# RFID_reader_circuit.net
KiCad netlist of a schematic drawn in Altium Designer
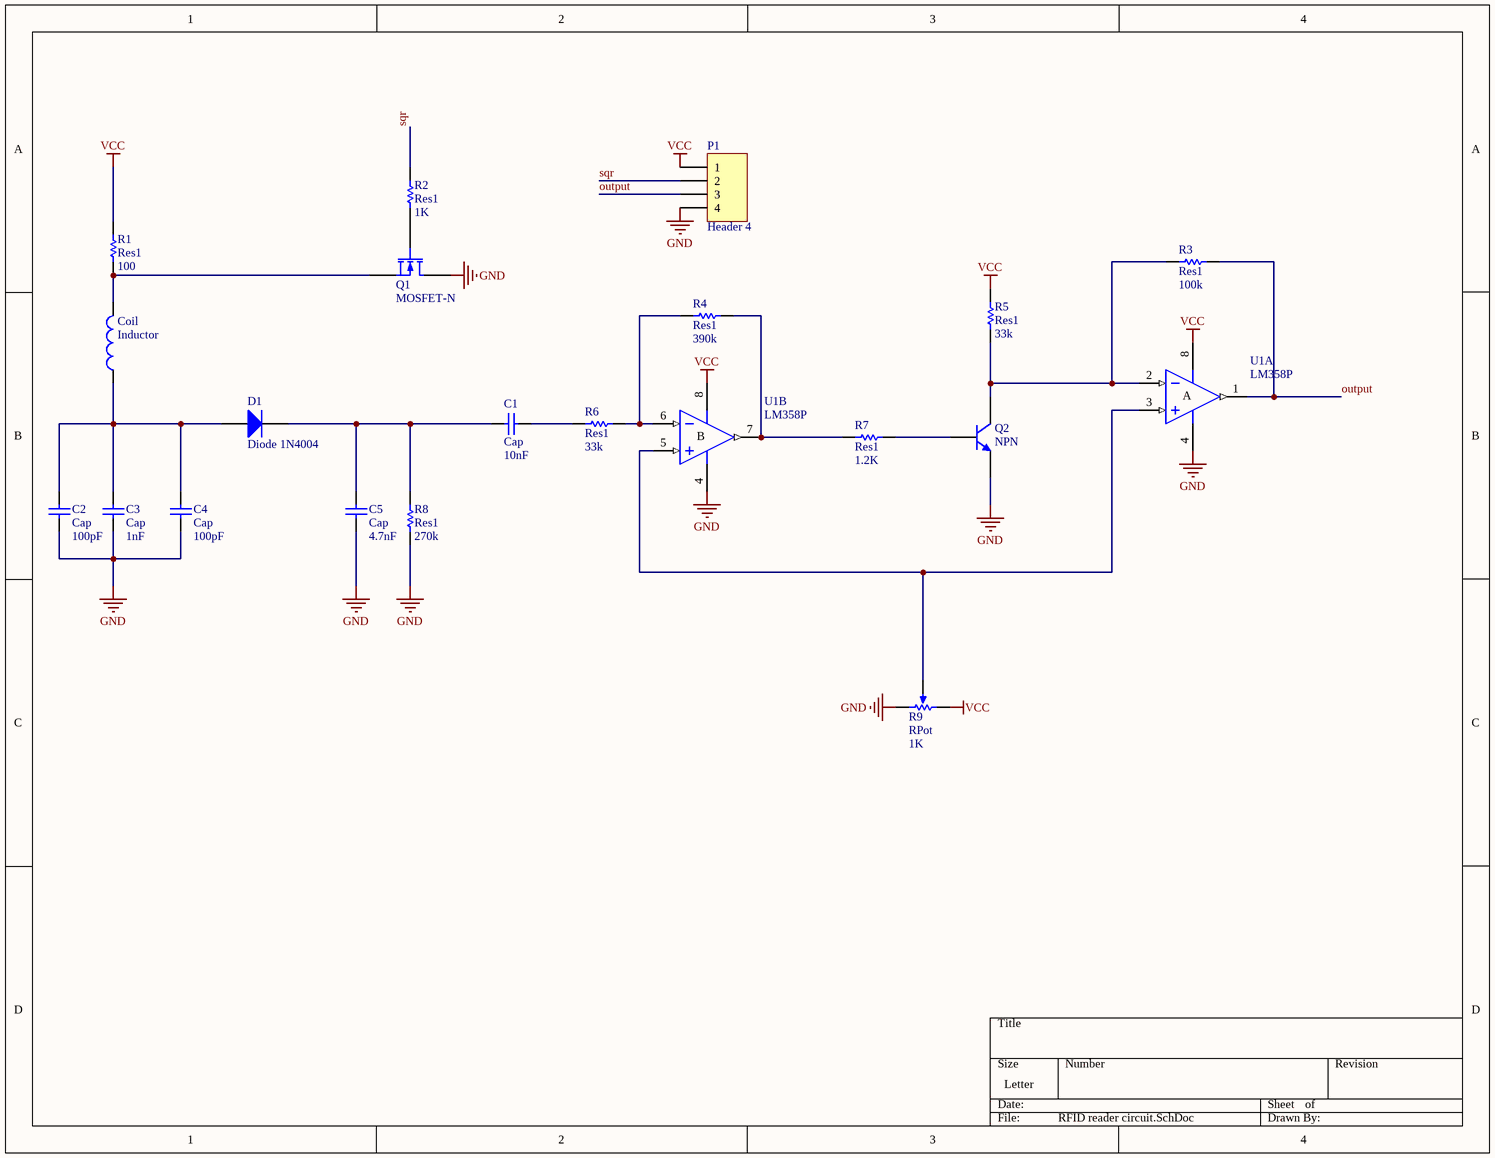
[diagram p0: RFID reader circuit.SchDoc]

(export (version "E")
  (design (tool "Eeschema 10.0.6"))
  (components
    (comp (ref "C1")
      (value "Cap")
      (footprint "RAD-0.3")
      (description "Capacitor")
      (fields (field (name "ALTIUM_VALUE") "10nF") (field (name "PUBLISHER") "Altium Limited"))
      (libsource (lib "Miscellaneous Devices") (part "Cap"))
    )
    (comp (ref "C2")
      (value "Cap")
      (footprint "RAD-0.3")
      (description "Capacitor")
      (fields (field (name "ALTIUM_VALUE") "100pF") (field (name "PUBLISHER") "Altium Limited"))
      (libsource (lib "Miscellaneous Devices") (part "Cap"))
    )
    (comp (ref "C3")
      (value "Cap")
      (footprint "RAD-0.3")
      (description "Capacitor")
      (fields (field (name "ALTIUM_VALUE") "1nF") (field (name "PUBLISHER") "Altium Limited"))
      (libsource (lib "Miscellaneous Devices") (part "Cap"))
    )
    (comp (ref "C4")
      (value "Cap")
      (footprint "RAD-0.3")
      (description "Capacitor")
      (fields (field (name "ALTIUM_VALUE") "100pF") (field (name "PUBLISHER") "Altium Limited"))
      (libsource (lib "Miscellaneous Devices") (part "Cap"))
    )
    (comp (ref "C5")
      (value "Cap")
      (footprint "RAD-0.3")
      (description "Capacitor")
      (fields (field (name "ALTIUM_VALUE") "4.7nF") (field (name "PUBLISHER") "Altium Limited"))
      (libsource (lib "Miscellaneous Devices") (part "Cap"))
    )
    (comp (ref "Coil")
      (value "Inductor")
      (footprint "XTAL-2")
      (fields (field (name "PUBLISHER") "Altium Limited"))
      (libsource (lib "Miscellaneous Devices") (part "Inductor"))
    )
    (comp (ref "D1")
      (value "Diode 1N4004")
      (footprint "DO-41")
      (description "1 Amp General Purpose Rectifier")
      (fields (field (name "PUBLISHER") "Altium Limited"))
      (libsource (lib "Miscellaneous Devices") (part "Diode 1N4004"))
    )
    (comp (ref "P1")
      (value "Header 4")
      (footprint "HDR1X4")
      (description "Header, 4-Pin")
      (fields (field (name "PUBLISHER") "Altium Limited"))
      (libsource (lib "Miscellaneous Connectors") (part "Header 4"))
    )
    (comp (ref "Q1")
      (value "MOSFET-N")
      (footprint "E3")
      (description "N-Channel MOSFET")
      (fields (field (name "PUBLISHER") "Altium Limited"))
      (libsource (lib "Miscellaneous Devices") (part "MOSFET-N"))
    )
    (comp (ref "Q2")
      (value "NPN")
      (footprint "TO-226-AA")
      (description "NPN Bipolar Transistor")
      (fields (field (name "PUBLISHER") "Altium Limited"))
      (libsource (lib "Miscellaneous Devices") (part "NPN"))
    )
    (comp (ref "R1")
      (value "Res1")
      (footprint "AXIAL-0.3")
      (description "Resistor")
      (fields (field (name "ALTIUM_VALUE") "100") (field (name "PUBLISHER") "Altium Limited"))
      (libsource (lib "Miscellaneous Devices") (part "Res1"))
    )
    (comp (ref "R2")
      (value "Res1")
      (footprint "AXIAL-0.3")
      (description "Resistor")
      (fields (field (name "ALTIUM_VALUE") "1K") (field (name "PUBLISHER") "Altium Limited"))
      (libsource (lib "Miscellaneous Devices") (part "Res1"))
    )
    (comp (ref "R3")
      (value "Res1")
      (footprint "AXIAL-0.3")
      (description "Resistor")
      (fields (field (name "ALTIUM_VALUE") "100k") (field (name "PUBLISHER") "Altium Limited"))
      (libsource (lib "Miscellaneous Devices") (part "Res1"))
    )
    (comp (ref "R4")
      (value "Res1")
      (footprint "AXIAL-0.3")
      (description "Resistor")
      (fields (field (name "ALTIUM_VALUE") "390k") (field (name "PUBLISHER") "Altium Limited"))
      (libsource (lib "Miscellaneous Devices") (part "Res1"))
    )
    (comp (ref "R5")
      (value "Res1")
      (footprint "AXIAL-0.3")
      (description "Resistor")
      (fields (field (name "ALTIUM_VALUE") "33k") (field (name "PUBLISHER") "Altium Limited"))
      (libsource (lib "Miscellaneous Devices") (part "Res1"))
    )
    (comp (ref "R6")
      (value "Res1")
      (footprint "AXIAL-0.3")
      (description "Resistor")
      (fields (field (name "ALTIUM_VALUE") "33k") (field (name "PUBLISHER") "Altium Limited"))
      (libsource (lib "Miscellaneous Devices") (part "Res1"))
    )
    (comp (ref "R7")
      (value "Res1")
      (footprint "AXIAL-0.3")
      (description "Resistor")
      (fields (field (name "ALTIUM_VALUE") "1.2K") (field (name "PUBLISHER") "Altium Limited"))
      (libsource (lib "Miscellaneous Devices") (part "Res1"))
    )
    (comp (ref "R8")
      (value "Res1")
      (footprint "AXIAL-0.3")
      (description "Resistor")
      (fields (field (name "ALTIUM_VALUE") "270k") (field (name "PUBLISHER") "Altium Limited"))
      (libsource (lib "Miscellaneous Devices") (part "Res1"))
    )
    (comp (ref "R9")
      (value "RPot")
      (footprint "VR5")
      (description "Potentiometer")
      (fields (field (name "ALTIUM_VALUE") "1K") (field (name "PUBLISHER") "Altium Limited"))
      (libsource (lib "Miscellaneous Devices") (part "RPot"))
    )
    (comp (ref "U1")
      (value "LM358P")
      (footprint "P008")
      (description "Dual Operational Amplifier")
      (fields (field (name "PUBLISHER") "Altium Limited"))
      (libsource (lib "TI Operational Amplifier") (part "LM358P"))
    )
  )
  (nets
    (net (code "1") (name "/output") (class "Default")
      (node (ref "P1") (pin "3") (pinfunction "3_3") (pintype "passive"))
      (node (ref "R3") (pin "1") (pinfunction "1_1") (pintype "passive"))
      (node (ref "U1") (pin "1") (pinfunction "OUT_1") (pintype "output"))
    )
    (net (code "2") (name "/sqr") (class "Default")
      (node (ref "P1") (pin "2") (pinfunction "2_2") (pintype "passive"))
      (node (ref "R2") (pin "2") (pinfunction "2_2") (pintype "passive"))
    )
    (net (code "3") (name "GND") (class "Default")
      (node (ref "C2") (pin "1") (pinfunction "1_1") (pintype "passive"))
      (node (ref "C3") (pin "1") (pinfunction "1_1") (pintype "passive"))
      (node (ref "C4") (pin "1") (pinfunction "1_1") (pintype "passive"))
      (node (ref "C5") (pin "1") (pinfunction "1_1") (pintype "passive"))
      (node (ref "P1") (pin "4") (pinfunction "4_4") (pintype "passive"))
      (node (ref "Q1") (pin "1") (pinfunction "D_1") (pintype "passive"))
      (node (ref "Q2") (pin "3") (pinfunction "E_3") (pintype "passive"))
      (node (ref "R8") (pin "2") (pinfunction "2_2") (pintype "passive"))
      (node (ref "R9") (pin "2") (pinfunction "BOT_2") (pintype "passive"))
      (node (ref "U1") (pin "4") (pinfunction "V-_4") (pintype "power_in"))
    )
    (net (code "4") (name "Net-(C1-Pad1)") (class "Default")
      (node (ref "C1") (pin "1") (pinfunction "1_1") (pintype "passive"))
      (node (ref "R6") (pin "1") (pinfunction "1_1") (pintype "passive"))
    )
    (net (code "5") (name "Net-(D1-A)") (class "Default")
      (node (ref "C2") (pin "2") (pinfunction "2_2") (pintype "passive"))
      (node (ref "C3") (pin "2") (pinfunction "2_2") (pintype "passive"))
      (node (ref "C4") (pin "2") (pinfunction "2_2") (pintype "passive"))
      (node (ref "Coil") (pin "1") (pinfunction "1_1") (pintype "passive"))
      (node (ref "D1") (pin "1") (pinfunction "A_1") (pintype "passive"))
    )
    (net (code "6") (name "Net-(D1-K)") (class "Default")
      (node (ref "C1") (pin "2") (pinfunction "2_2") (pintype "passive"))
      (node (ref "C5") (pin "2") (pinfunction "2_2") (pintype "passive"))
      (node (ref "D1") (pin "2") (pinfunction "K_2") (pintype "passive"))
      (node (ref "R8") (pin "1") (pinfunction "1_1") (pintype "passive"))
    )
    (net (code "7") (name "Net-(Q1-G)") (class "Default")
      (node (ref "Q1") (pin "2") (pinfunction "G_2") (pintype "passive"))
      (node (ref "R2") (pin "1") (pinfunction "1_1") (pintype "passive"))
    )
    (net (code "8") (name "Net-(Q1-S)") (class "Default")
      (node (ref "Coil") (pin "2") (pinfunction "2_2") (pintype "passive"))
      (node (ref "Q1") (pin "3") (pinfunction "S_3") (pintype "passive"))
      (node (ref "R1") (pin "1") (pinfunction "1_1") (pintype "passive"))
    )
    (net (code "9") (name "Net-(Q2-B)") (class "Default")
      (node (ref "Q2") (pin "2") (pinfunction "B_2") (pintype "passive"))
      (node (ref "R7") (pin "2") (pinfunction "2_2") (pintype "passive"))
    )
    (net (code "10") (name "Net-(Q2-C)") (class "Default")
      (node (ref "Q2") (pin "1") (pinfunction "C_1") (pintype "passive"))
      (node (ref "R3") (pin "2") (pinfunction "2_2") (pintype "passive"))
      (node (ref "R5") (pin "1") (pinfunction "1_1") (pintype "passive"))
      (node (ref "U1") (pin "2") (pinfunction "IN-_2") (pintype "input"))
    )
    (net (code "11") (name "Net-(R9-TAP)") (class "Default")
      (node (ref "R9") (pin "3") (pinfunction "TAP_3") (pintype "passive"))
      (node (ref "U1") (pin "3") (pinfunction "IN+_3") (pintype "input"))
      (node (ref "U1") (pin "5") (pinfunction "IN+_5") (pintype "input"))
    )
    (net (code "12") (name "Net-(U1B-IN-)") (class "Default")
      (node (ref "R4") (pin "1") (pinfunction "1_1") (pintype "passive"))
      (node (ref "R6") (pin "2") (pinfunction "2_2") (pintype "passive"))
      (node (ref "U1") (pin "6") (pinfunction "IN-_6") (pintype "input"))
    )
    (net (code "13") (name "Net-(U1B-OUT)") (class "Default")
      (node (ref "R4") (pin "2") (pinfunction "2_2") (pintype "passive"))
      (node (ref "R7") (pin "1") (pinfunction "1_1") (pintype "passive"))
      (node (ref "U1") (pin "7") (pinfunction "OUT_7") (pintype "output"))
    )
    (net (code "14") (name "VCC") (class "Default")
      (node (ref "P1") (pin "1") (pinfunction "1_1") (pintype "passive"))
      (node (ref "R1") (pin "2") (pinfunction "2_2") (pintype "passive"))
      (node (ref "R5") (pin "2") (pinfunction "2_2") (pintype "passive"))
      (node (ref "R9") (pin "1") (pinfunction "TOP_1") (pintype "passive"))
      (node (ref "U1") (pin "8") (pinfunction "V+_8") (pintype "power_in"))
    )
  )
)
